# LB_BIT_o1_LED-v02_rev1.net
KiCad netlist of a schematic drawn in EAGLE
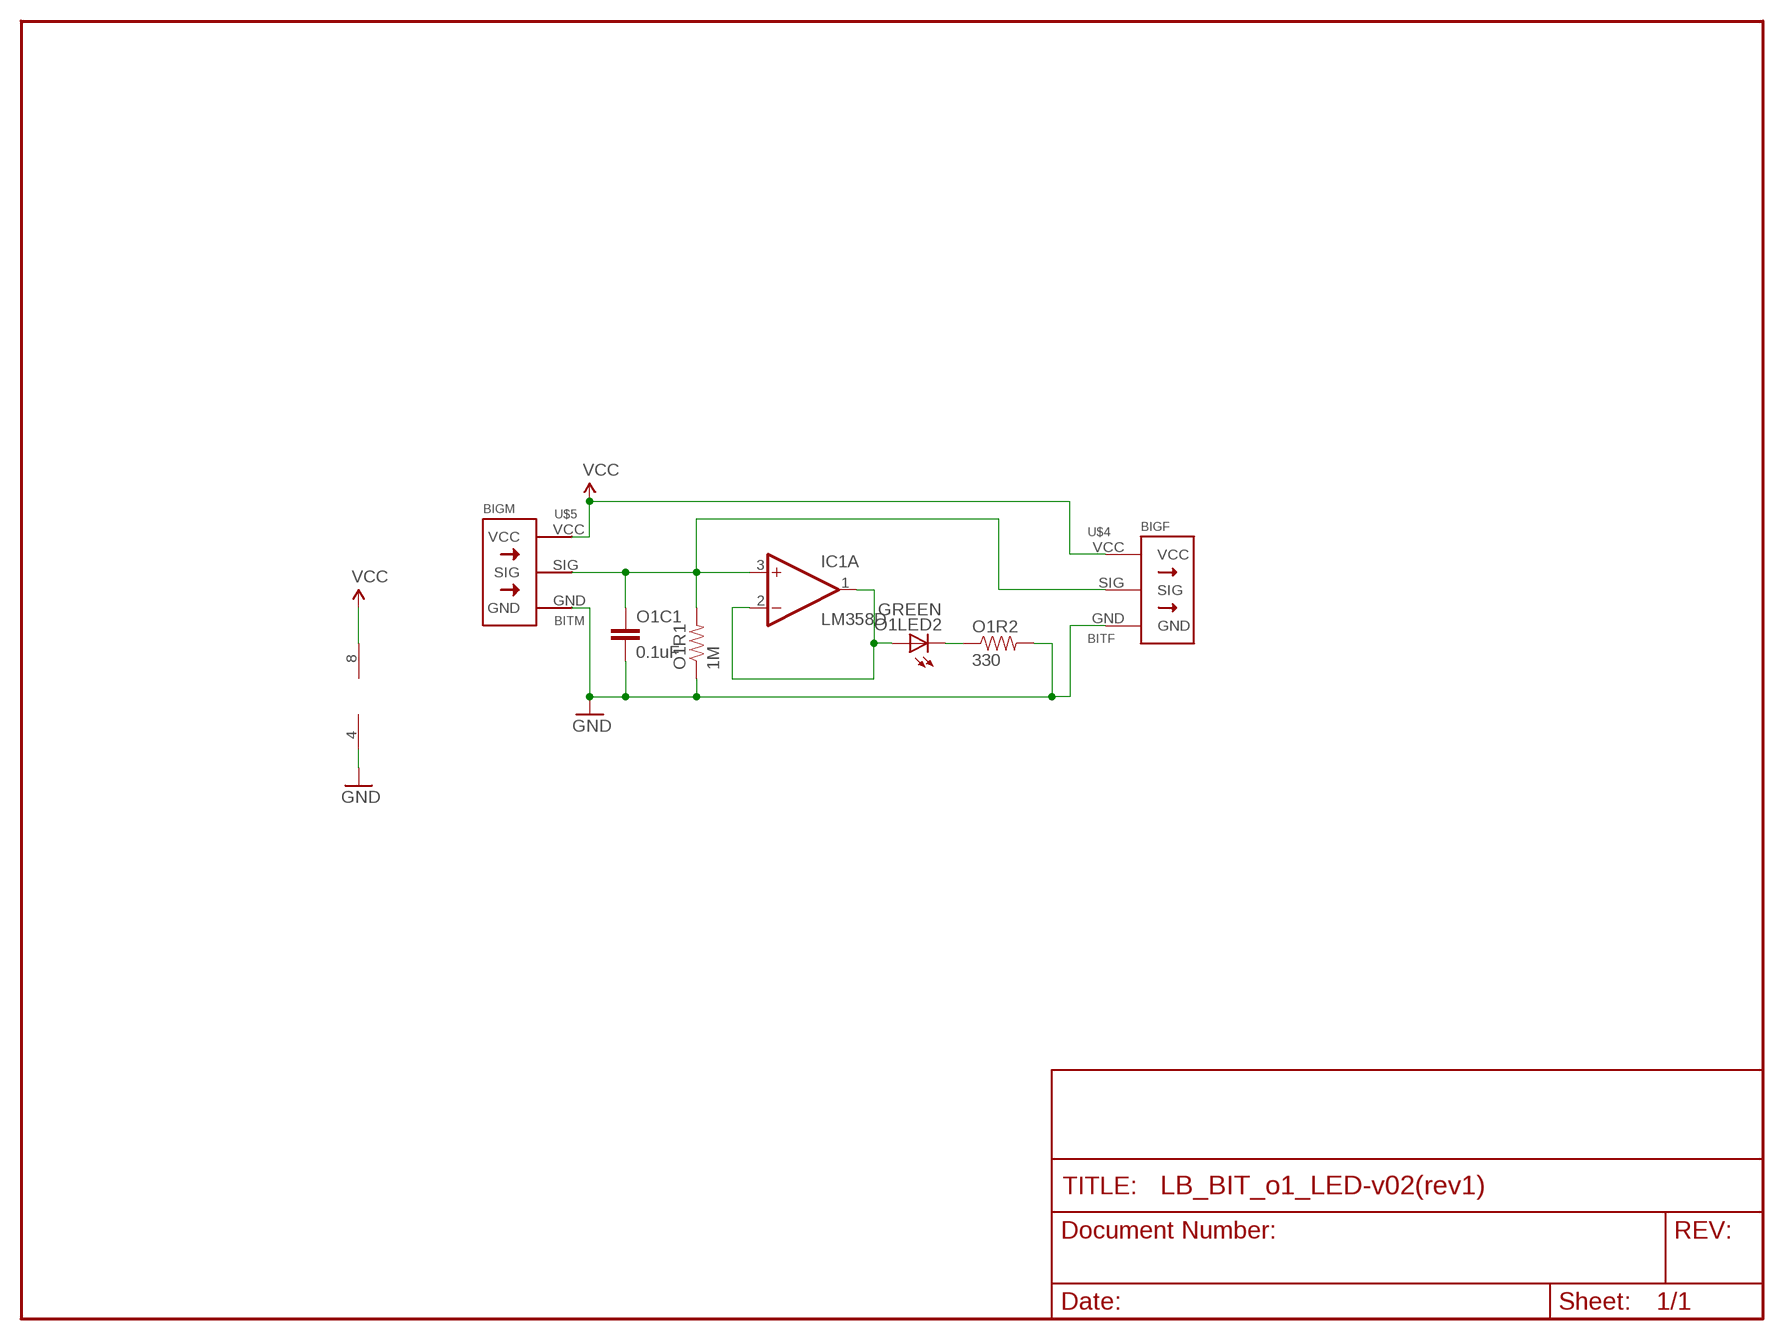
[diagram p0: schematic, sheet 1]

(export (version "E")
  (design (tool "Eeschema 10.0.6"))
  (components
    (comp (ref "IC1")
      (value "LM358D")
      (footprint "eagle-import:SO08")
      (libsource (lib "eagle-import") (part "LM358D"))
    )
    (comp (ref "O1C1")
      (value "0.1uF")
      (footprint "eagle-import:1206")
      (libsource (lib "eagle-import") (part "CAP1206"))
    )
    (comp (ref "O1LED2")
      (value "GREEN")
      (footprint "eagle-import:LED10MM")
      (libsource (lib "eagle-import") (part "LED10MM"))
    )
    (comp (ref "O1R1")
      (value "1M")
      (footprint "eagle-import:0805")
      (libsource (lib "eagle-import") (part "RESISTOR"))
    )
    (comp (ref "O1R2")
      (value "330")
      (footprint "eagle-import:0805")
      (libsource (lib "eagle-import") (part "RESISTOR"))
    )
    (comp (ref "U$4")
      (value "BITF")
      (footprint "eagle-import:BITM")
      (libsource (lib "eagle-import") (part "BITF"))
    )
    (comp (ref "U$5")
      (value "BITM")
      (footprint "eagle-import:BITM")
      (libsource (lib "eagle-import") (part "BITM"))
    )
  )
  (nets
    (net (code "1") (name "GND") (class "Default")
      (node (ref "IC1") (pin "4") (pinfunction "V-_4") (pintype "power_in"))
      (node (ref "O1C1") (pin "2") (pinfunction "2_2") (pintype "passive"))
      (node (ref "O1R1") (pin "1") (pinfunction "1_1") (pintype "passive"))
      (node (ref "O1R2") (pin "2") (pinfunction "2_2") (pintype "passive"))
      (node (ref "U$4") (pin "GND") (pinfunction "GND_GND") (pintype "bidirectional"))
      (node (ref "U$5") (pin "GND") (pinfunction "GND_GND") (pintype "bidirectional"))
    )
    (net (code "2") (name "Net-(IC1A-+IN)") (class "Default")
      (node (ref "IC1") (pin "3") (pinfunction "+IN_3") (pintype "input"))
      (node (ref "O1C1") (pin "1") (pinfunction "1_1") (pintype "passive"))
      (node (ref "O1R1") (pin "2") (pinfunction "2_2") (pintype "passive"))
      (node (ref "U$4") (pin "SIG") (pinfunction "SIG_SIG") (pintype "bidirectional"))
      (node (ref "U$5") (pin "SIG") (pinfunction "SIG_SIG") (pintype "bidirectional"))
    )
    (net (code "3") (name "Net-(IC1A--IN)") (class "Default")
      (node (ref "IC1") (pin "1") (pinfunction "OUT_1") (pintype "output"))
      (node (ref "IC1") (pin "2") (pinfunction "-IN_2") (pintype "input"))
      (node (ref "O1LED2") (pin "A") (pinfunction "A_A") (pintype "passive"))
    )
    (net (code "4") (name "Net-(O1LED2-PadC)") (class "Default")
      (node (ref "O1LED2") (pin "C") (pinfunction "C_C") (pintype "passive"))
      (node (ref "O1R2") (pin "1") (pinfunction "1_1") (pintype "passive"))
    )
    (net (code "5") (name "VCC") (class "Default")
      (node (ref "IC1") (pin "8") (pinfunction "V+_8") (pintype "power_in"))
      (node (ref "U$4") (pin "VCC") (pinfunction "VCC_VCC") (pintype "bidirectional"))
      (node (ref "U$5") (pin "VCC") (pinfunction "VCC_VCC") (pintype "bidirectional"))
    )
  )
)
